# Speed_Controller.net
KiCad netlist of a schematic drawn in Altium Designer
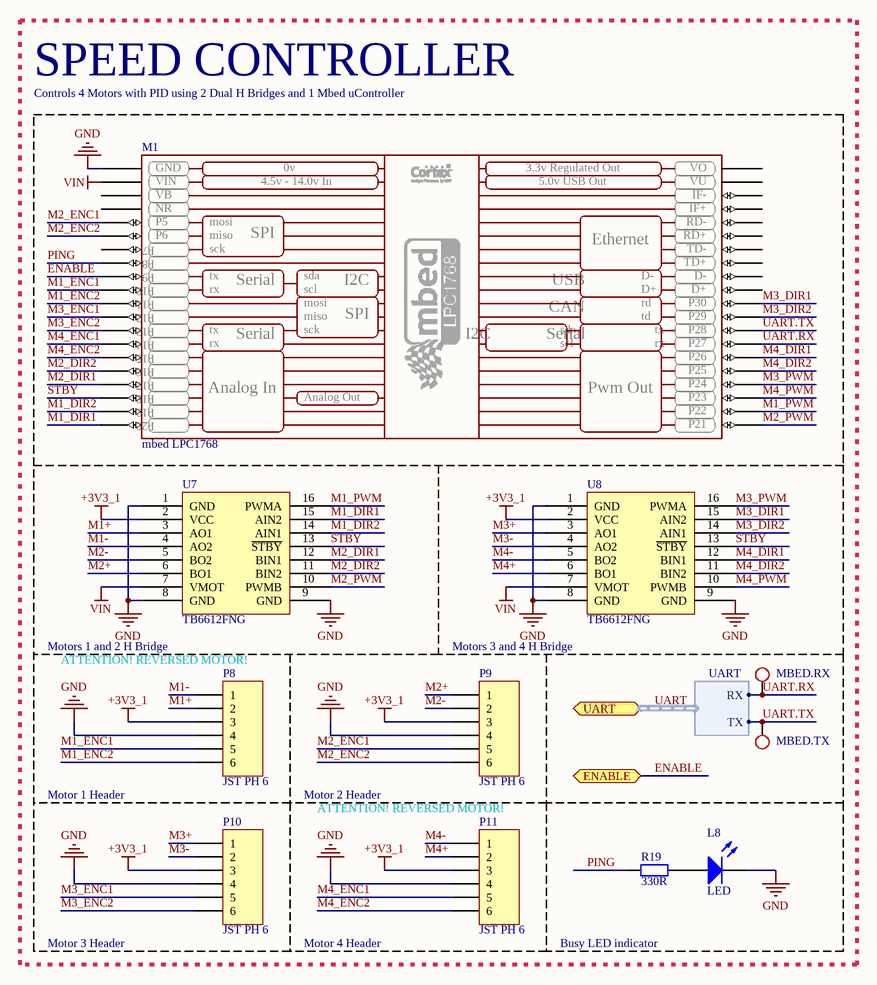
[diagram p0: Speed Controller.SchDoc]

(export (version "E")
  (design (tool "Eeschema 10.0.6"))
  (components
    (comp (ref "L8") (value "LED") (footprint "LED0805") (libsource (lib "CustomLibrary") (part "LED")))
    (comp (ref "M1")
      (value "mbed LPC1768")
      (footprint "DIP40-LARGE")
      (libsource (lib "CustomLibrary") (part "mbed LPC1768"))
    )
    (comp (ref "MBED.RX")
      (value "Test Point")
      (footprint "TP1")
      (description "Test Point for Osciloscope measurements")
      (libsource (lib "CustomLibrary") (part "Test Point"))
    )
    (comp (ref "MBED.TX")
      (value "Test Point")
      (footprint "TP1")
      (description "Test Point for Osciloscope measurements")
      (libsource (lib "CustomLibrary") (part "Test Point"))
    )
    (comp (ref "P8")
      (value "JST PH 6")
      (footprint "B6B-PH-K")
      (libsource (lib "CustomLibrary") (part "JST PH 6"))
    )
    (comp (ref "P9")
      (value "JST PH 6")
      (footprint "B6B-PH-K")
      (libsource (lib "CustomLibrary") (part "JST PH 6"))
    )
    (comp (ref "P10")
      (value "JST PH 6")
      (footprint "B6B-PH-K")
      (libsource (lib "CustomLibrary") (part "JST PH 6"))
    )
    (comp (ref "P11")
      (value "JST PH 6")
      (footprint "B6B-PH-K")
      (libsource (lib "CustomLibrary") (part "JST PH 6"))
    )
    (comp (ref "R19") (value "330R") (footprint "RES1206") (libsource (lib "CustomLibrary") (part "RES")))
    (comp (ref "U7")
      (value "TB6612FNG")
      (footprint "TB6612FNG")
      (description "H BRIDGE")
      (libsource (lib "CustomLibrary") (part "TB6612FNG"))
    )
    (comp (ref "U8")
      (value "TB6612FNG")
      (footprint "TB6612FNG")
      (description "H BRIDGE")
      (libsource (lib "CustomLibrary") (part "TB6612FNG"))
    )
  )
  (nets
    (net (code "2") (name "+3V3_1") (class "Default")
      (node (ref "P10") (pin "3") (pinfunction "3_3") (pintype "passive"))
      (node (ref "P11") (pin "3") (pinfunction "3_3") (pintype "passive"))
      (node (ref "P8") (pin "3") (pinfunction "3_3") (pintype "passive"))
      (node (ref "P9") (pin "3") (pinfunction "3_3") (pintype "passive"))
      (node (ref "U7") (pin "2") (pinfunction "VCC_2") (pintype "passive"))
      (node (ref "U8") (pin "2") (pinfunction "VCC_2") (pintype "passive"))
    )
    (net (code "3") (name "/ENABLE") (class "Default")
      (node (ref "M1") (pin "9") (pinfunction "P9_9") (pintype "bidirectional"))
    )
    (net (code "4") (name "/M1+") (class "Default")
      (node (ref "P8") (pin "2") (pinfunction "2_2") (pintype "passive"))
      (node (ref "U7") (pin "3") (pinfunction "AO1_3") (pintype "passive"))
    )
    (net (code "5") (name "/M1-") (class "Default")
      (node (ref "P8") (pin "1") (pinfunction "1_1") (pintype "passive"))
      (node (ref "U7") (pin "4") (pinfunction "AO2_4") (pintype "passive"))
    )
    (net (code "6") (name "/M1_DIR1") (class "Default")
      (node (ref "M1") (pin "20") (pinfunction "P20_20") (pintype "bidirectional"))
      (node (ref "U7") (pin "15") (pinfunction "AIN2_15") (pintype "passive"))
    )
    (net (code "7") (name "/M1_DIR2") (class "Default")
      (node (ref "M1") (pin "19") (pinfunction "P19_19") (pintype "bidirectional"))
      (node (ref "U7") (pin "14") (pinfunction "AIN1_14") (pintype "passive"))
    )
    (net (code "8") (name "/M1_ENC1") (class "Default")
      (node (ref "M1") (pin "10") (pinfunction "P10_10") (pintype "bidirectional"))
      (node (ref "P8") (pin "5") (pinfunction "5_5") (pintype "passive"))
    )
    (net (code "9") (name "/M1_ENC2") (class "Default")
      (node (ref "M1") (pin "11") (pinfunction "P11_11") (pintype "bidirectional"))
      (node (ref "P8") (pin "6") (pinfunction "6_6") (pintype "passive"))
    )
    (net (code "10") (name "/M1_PWM") (class "Default")
      (node (ref "M1") (pin "22") (pinfunction "P22_22") (pintype "bidirectional"))
      (node (ref "U7") (pin "16") (pinfunction "PWMA_16") (pintype "passive"))
    )
    (net (code "11") (name "/M2+") (class "Default")
      (node (ref "P9") (pin "1") (pinfunction "1_1") (pintype "passive"))
      (node (ref "U7") (pin "6") (pinfunction "BO1_6") (pintype "passive"))
    )
    (net (code "12") (name "/M2-") (class "Default")
      (node (ref "P9") (pin "2") (pinfunction "2_2") (pintype "passive"))
      (node (ref "U7") (pin "5") (pinfunction "BO2_5") (pintype "passive"))
    )
    (net (code "13") (name "/M2_DIR1") (class "Default")
      (node (ref "M1") (pin "17") (pinfunction "P17_17") (pintype "bidirectional"))
      (node (ref "U7") (pin "12") (pinfunction "BIN1_12") (pintype "passive"))
    )
    (net (code "14") (name "/M2_DIR2") (class "Default")
      (node (ref "M1") (pin "16") (pinfunction "P16_16") (pintype "bidirectional"))
      (node (ref "U7") (pin "11") (pinfunction "BIN2_11") (pintype "passive"))
    )
    (net (code "15") (name "/M2_ENC1") (class "Default")
      (node (ref "M1") (pin "5") (pinfunction "P5_5") (pintype "bidirectional"))
      (node (ref "P9") (pin "5") (pinfunction "5_5") (pintype "passive"))
    )
    (net (code "16") (name "/M2_ENC2") (class "Default")
      (node (ref "M1") (pin "6") (pinfunction "P6_6") (pintype "bidirectional"))
      (node (ref "P9") (pin "6") (pinfunction "6_6") (pintype "passive"))
    )
    (net (code "17") (name "/M2_PWM") (class "Default")
      (node (ref "M1") (pin "21") (pinfunction "P21_21") (pintype "bidirectional"))
      (node (ref "U7") (pin "10") (pinfunction "PWMB_10") (pintype "passive"))
    )
    (net (code "18") (name "/M3+") (class "Default")
      (node (ref "P10") (pin "1") (pinfunction "1_1") (pintype "passive"))
      (node (ref "U8") (pin "3") (pinfunction "AO1_3") (pintype "passive"))
    )
    (net (code "19") (name "/M3-") (class "Default")
      (node (ref "P10") (pin "2") (pinfunction "2_2") (pintype "passive"))
      (node (ref "U8") (pin "4") (pinfunction "AO2_4") (pintype "passive"))
    )
    (net (code "20") (name "/M3_DIR1") (class "Default")
      (node (ref "M1") (pin "30") (pinfunction "P30_30") (pintype "bidirectional"))
      (node (ref "U8") (pin "15") (pinfunction "AIN2_15") (pintype "passive"))
    )
    (net (code "21") (name "/M3_DIR2") (class "Default")
      (node (ref "M1") (pin "29") (pinfunction "P29_29") (pintype "bidirectional"))
      (node (ref "U8") (pin "14") (pinfunction "AIN1_14") (pintype "passive"))
    )
    (net (code "22") (name "/M3_ENC1") (class "Default")
      (node (ref "M1") (pin "12") (pinfunction "P12_12") (pintype "bidirectional"))
      (node (ref "P10") (pin "5") (pinfunction "5_5") (pintype "passive"))
    )
    (net (code "23") (name "/M3_ENC2") (class "Default")
      (node (ref "M1") (pin "13") (pinfunction "P13_13") (pintype "bidirectional"))
      (node (ref "P10") (pin "6") (pinfunction "6_6") (pintype "passive"))
    )
    (net (code "24") (name "/M3_PWM") (class "Default")
      (node (ref "M1") (pin "24") (pinfunction "P24_24") (pintype "bidirectional"))
      (node (ref "U8") (pin "16") (pinfunction "PWMA_16") (pintype "passive"))
    )
    (net (code "25") (name "/M4+") (class "Default")
      (node (ref "P11") (pin "2") (pinfunction "2_2") (pintype "passive"))
      (node (ref "U8") (pin "6") (pinfunction "BO1_6") (pintype "passive"))
    )
    (net (code "26") (name "/M4-") (class "Default")
      (node (ref "P11") (pin "1") (pinfunction "1_1") (pintype "passive"))
      (node (ref "U8") (pin "5") (pinfunction "BO2_5") (pintype "passive"))
    )
    (net (code "27") (name "/M4_DIR1") (class "Default")
      (node (ref "M1") (pin "26") (pinfunction "P26_26") (pintype "bidirectional"))
      (node (ref "U8") (pin "12") (pinfunction "BIN1_12") (pintype "passive"))
    )
    (net (code "28") (name "/M4_DIR2") (class "Default")
      (node (ref "M1") (pin "25") (pinfunction "P25_25") (pintype "bidirectional"))
      (node (ref "U8") (pin "11") (pinfunction "BIN2_11") (pintype "passive"))
    )
    (net (code "29") (name "/M4_ENC1") (class "Default")
      (node (ref "M1") (pin "14") (pinfunction "P14_14") (pintype "bidirectional"))
      (node (ref "P11") (pin "5") (pinfunction "5_5") (pintype "passive"))
    )
    (net (code "30") (name "/M4_ENC2") (class "Default")
      (node (ref "M1") (pin "15") (pinfunction "P15_15") (pintype "bidirectional"))
      (node (ref "P11") (pin "6") (pinfunction "6_6") (pintype "passive"))
    )
    (net (code "31") (name "/M4_PWM") (class "Default")
      (node (ref "M1") (pin "23") (pinfunction "P23_23") (pintype "bidirectional"))
      (node (ref "U8") (pin "10") (pinfunction "PWMB_10") (pintype "passive"))
    )
    (net (code "32") (name "/PING") (class "Default")
      (node (ref "M1") (pin "8") (pinfunction "P8_8") (pintype "bidirectional"))
      (node (ref "R19") (pin "2") (pinfunction "2_2") (pintype "passive"))
    )
    (net (code "33") (name "/STBY") (class "Default")
      (node (ref "M1") (pin "18") (pinfunction "P18_18") (pintype "bidirectional"))
      (node (ref "U7") (pin "13") (pinfunction "~{STBY}_13") (pintype "passive"))
      (node (ref "U8") (pin "13") (pinfunction "~{STBY}_13") (pintype "passive"))
    )
    (net (code "34") (name "/UART.RX") (class "Default")
      (node (ref "M1") (pin "27") (pinfunction "P27_27") (pintype "bidirectional"))
      (node (ref "MBED.RX") (pin "1") (pinfunction "1_1") (pintype "passive"))
    )
    (net (code "35") (name "/UART.TX") (class "Default")
      (node (ref "M1") (pin "28") (pinfunction "P28_28") (pintype "bidirectional"))
      (node (ref "MBED.TX") (pin "1") (pinfunction "1_1") (pintype "passive"))
    )
    (net (code "37") (name "GND") (class "Default")
      (node (ref "L8") (pin "2") (pinfunction "K_2") (pintype "passive"))
      (node (ref "M1") (pin "1") (pinfunction "GND_1") (pintype "power_in"))
      (node (ref "P10") (pin "4") (pinfunction "4_4") (pintype "passive"))
      (node (ref "P11") (pin "4") (pinfunction "4_4") (pintype "passive"))
      (node (ref "P8") (pin "4") (pinfunction "4_4") (pintype "passive"))
      (node (ref "P9") (pin "4") (pinfunction "4_4") (pintype "passive"))
      (node (ref "U7") (pin "1") (pinfunction "GND_1") (pintype "passive"))
      (node (ref "U7") (pin "8") (pinfunction "GND_8") (pintype "passive"))
      (node (ref "U7") (pin "9") (pinfunction "GND_9") (pintype "passive"))
      (node (ref "U8") (pin "1") (pinfunction "GND_1") (pintype "passive"))
      (node (ref "U8") (pin "8") (pinfunction "GND_8") (pintype "passive"))
      (node (ref "U8") (pin "9") (pinfunction "GND_9") (pintype "passive"))
    )
    (net (code "38") (name "Net-(L8-A)") (class "Default")
      (node (ref "L8") (pin "1") (pinfunction "A_1") (pintype "passive"))
      (node (ref "R19") (pin "1") (pinfunction "1_1") (pintype "passive"))
    )
    (net (code "39") (name "VIN") (class "Default")
      (node (ref "M1") (pin "2") (pinfunction "VIN_2") (pintype "power_in"))
      (node (ref "U7") (pin "7") (pinfunction "VMOT_7") (pintype "passive"))
      (node (ref "U8") (pin "7") (pinfunction "VMOT_7") (pintype "passive"))
    )
    (net (code "40") (name "unconnected-(M1-D+-Pad31)") (class "Default")
      (node (ref "M1") (pin "31") (pinfunction "D+_31") (pintype "bidirectional"))
    )
    (net (code "41") (name "unconnected-(M1-D--Pad32)") (class "Default")
      (node (ref "M1") (pin "32") (pinfunction "D-_32") (pintype "bidirectional"))
    )
    (net (code "42") (name "unconnected-(M1-IF+-Pad37)") (class "Default")
      (node (ref "M1") (pin "37") (pinfunction "IF+_37") (pintype "bidirectional"))
    )
    (net (code "43") (name "unconnected-(M1-IF--Pad38)") (class "Default")
      (node (ref "M1") (pin "38") (pinfunction "IF-_38") (pintype "bidirectional"))
    )
    (net (code "44") (name "unconnected-(M1-NR-Pad4)") (class "Default")
      (node (ref "M1") (pin "4") (pinfunction "NR_4") (pintype "power_in"))
    )
    (net (code "45") (name "unconnected-(M1-P7-Pad7)") (class "Default")
      (node (ref "M1") (pin "7") (pinfunction "P7_7") (pintype "bidirectional"))
    )
    (net (code "46") (name "unconnected-(M1-RD+-Pad35)") (class "Default")
      (node (ref "M1") (pin "35") (pinfunction "RD+_35") (pintype "bidirectional"))
    )
    (net (code "47") (name "unconnected-(M1-RD--Pad36)") (class "Default")
      (node (ref "M1") (pin "36") (pinfunction "RD-_36") (pintype "bidirectional"))
    )
    (net (code "48") (name "unconnected-(M1-TD+-Pad33)") (class "Default")
      (node (ref "M1") (pin "33") (pinfunction "TD+_33") (pintype "bidirectional"))
    )
    (net (code "49") (name "unconnected-(M1-TD--Pad34)") (class "Default")
      (node (ref "M1") (pin "34") (pinfunction "TD-_34") (pintype "bidirectional"))
    )
    (net (code "50") (name "unconnected-(M1-VB-Pad3)") (class "Default")
      (node (ref "M1") (pin "3") (pinfunction "VB_3") (pintype "power_in"))
    )
    (net (code "51") (name "unconnected-(M1-VO-Pad40)") (class "Default")
      (node (ref "M1") (pin "40") (pinfunction "VO_40") (pintype "power_in"))
    )
    (net (code "52") (name "unconnected-(M1-VU-Pad39)") (class "Default")
      (node (ref "M1") (pin "39") (pinfunction "VU_39") (pintype "power_in"))
    )
  )
)
